# main.net
KiCad netlist of a schematic drawn in EAGLE
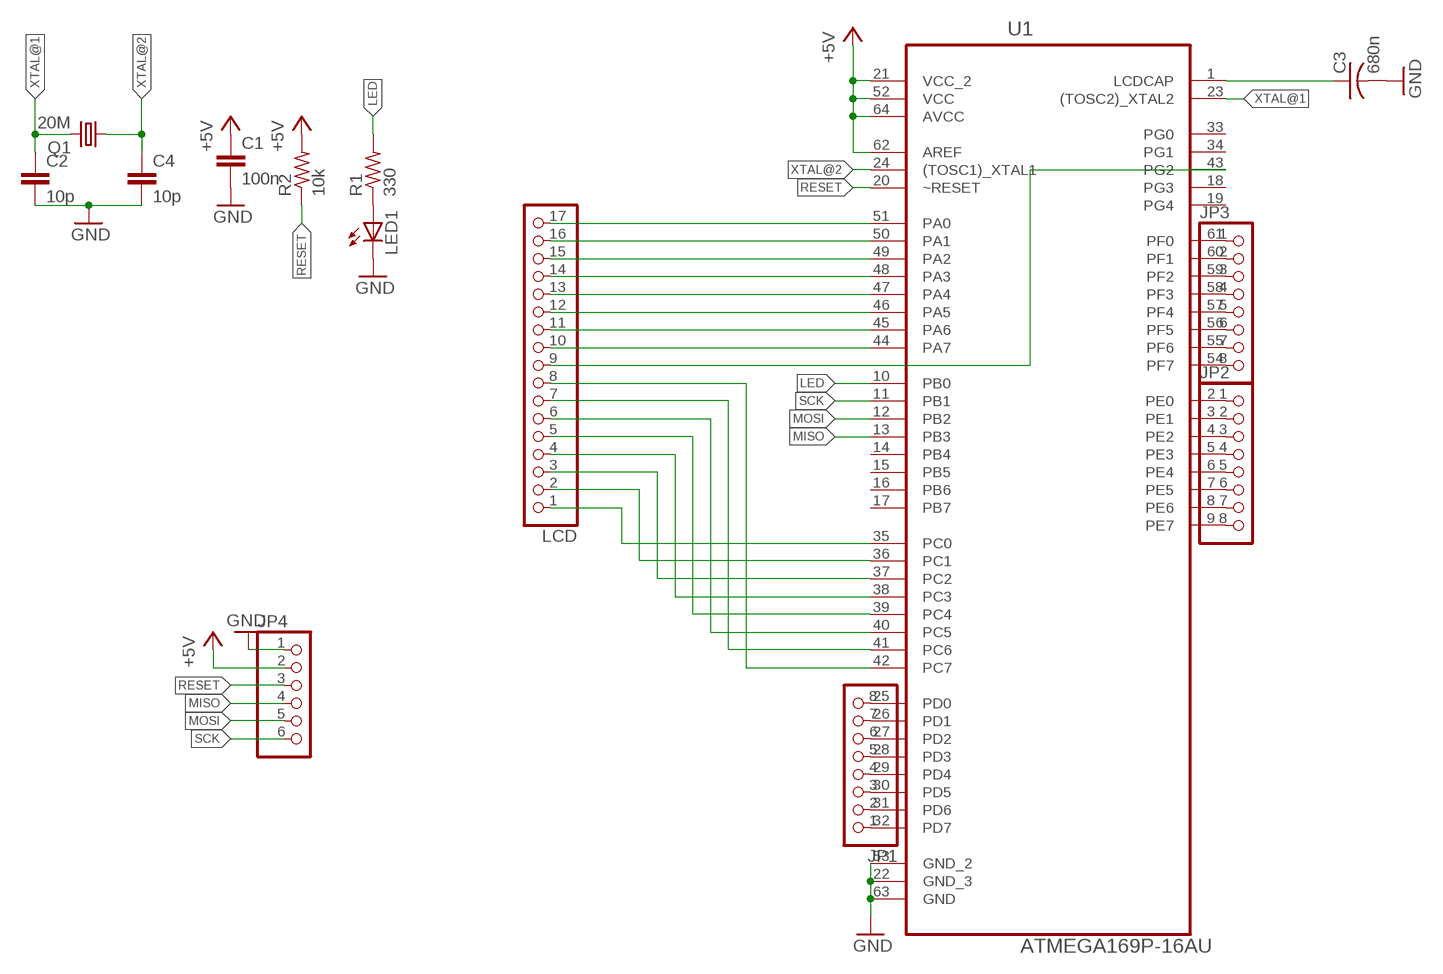
[diagram p0: schematic, sheet 1]

(export (version "E")
  (design (tool "Eeschema 10.0.6"))
  (components
    (comp (ref "C1")
      (value "100n")
      (footprint "eagle-import:C0603")
      (libsource (lib "eagle-import") (part "C-EUC0603"))
    )
    (comp (ref "C2")
      (value "10p")
      (footprint "eagle-import:C0603")
      (libsource (lib "eagle-import") (part "C-EUC0603"))
    )
    (comp (ref "C3")
      (value "680n")
      (footprint "eagle-import:C025-025X050")
      (libsource (lib "eagle-import") (part "C-US025-025X050"))
    )
    (comp (ref "C4")
      (value "10p")
      (footprint "eagle-import:C0603")
      (libsource (lib "eagle-import") (part "C-EUC0603"))
    )
    (comp (ref "JP1")
      (value "PINHD-1X8/90")
      (footprint "eagle-import:1X08_90")
      (libsource (lib "eagle-import") (part "PINHD-1X8/90"))
    )
    (comp (ref "JP2")
      (value "PINHD-1X8/90")
      (footprint "eagle-import:1X08_90")
      (libsource (lib "eagle-import") (part "PINHD-1X8/90"))
    )
    (comp (ref "JP3")
      (value "PINHD-1X8/90")
      (footprint "eagle-import:1X08_90")
      (libsource (lib "eagle-import") (part "PINHD-1X8/90"))
    )
    (comp (ref "JP4")
      (value "PINHD-1X6")
      (footprint "eagle-import:1X06")
      (libsource (lib "eagle-import") (part "PINHD-1X6"))
    )
    (comp (ref "LCD")
      (value "PINHD-1X17")
      (footprint "eagle-import:1X17")
      (libsource (lib "eagle-import") (part "PINHD-1X17"))
    )
    (comp (ref "LED1")
      (value "LEDCHIPLED_0805")
      (footprint "eagle-import:CHIPLED_0805")
      (libsource (lib "eagle-import") (part "LEDCHIPLED_0805"))
    )
    (comp (ref "Q1")
      (value "20M")
      (footprint "eagle-import:HC49UP")
      (libsource (lib "eagle-import") (part "CRYSTALHC49UP"))
    )
    (comp (ref "R1")
      (value "330")
      (footprint "eagle-import:R0603")
      (libsource (lib "eagle-import") (part "R-US_R0603"))
    )
    (comp (ref "R2")
      (value "10k")
      (footprint "eagle-import:R0603")
      (libsource (lib "eagle-import") (part "R-US_R0603"))
    )
    (comp (ref "U1")
      (value "ATMEGA169P-16AU")
      (footprint "eagle-import:QFP80P1600X1600X120-64N")
      (libsource (lib "eagle-import") (part "ATMEGA169P-16AU"))
    )
  )
  (nets
    (net (code "1") (name "+5V") (class "Default")
      (node (ref "C1") (pin "1") (pinfunction "1_1") (pintype "passive"))
      (node (ref "JP4") (pin "2") (pinfunction "2_2") (pintype "passive"))
      (node (ref "R2") (pin "2") (pinfunction "2_2") (pintype "passive"))
      (node (ref "U1") (pin "21") (pinfunction "VCC_2_21") (pintype "power_in"))
      (node (ref "U1") (pin "52") (pinfunction "VCC_52") (pintype "power_in"))
      (node (ref "U1") (pin "62") (pinfunction "AREF_62") (pintype "input"))
      (node (ref "U1") (pin "64") (pinfunction "AVCC_64") (pintype "power_in"))
    )
    (net (code "2") (name "GND") (class "Default")
      (node (ref "C1") (pin "2") (pinfunction "2_2") (pintype "passive"))
      (node (ref "C2") (pin "2") (pinfunction "2_2") (pintype "passive"))
      (node (ref "C3") (pin "2") (pinfunction "2_2") (pintype "passive"))
      (node (ref "C4") (pin "2") (pinfunction "2_2") (pintype "passive"))
      (node (ref "JP4") (pin "1") (pinfunction "1_1") (pintype "passive"))
      (node (ref "LED1") (pin "C") (pinfunction "C_C") (pintype "passive"))
      (node (ref "U1") (pin "22") (pinfunction "GND_3_22") (pintype "passive"))
      (node (ref "U1") (pin "53") (pinfunction "GND_2_53") (pintype "passive"))
      (node (ref "U1") (pin "63") (pinfunction "GND_63") (pintype "passive"))
    )
    (net (code "3") (name "LED") (class "Default")
      (node (ref "R1") (pin "2") (pinfunction "2_2") (pintype "passive"))
      (node (ref "U1") (pin "10") (pinfunction "PB0_10") (pintype "bidirectional"))
    )
    (net (code "4") (name "MISO") (class "Default")
      (node (ref "JP4") (pin "4") (pinfunction "4_4") (pintype "passive"))
      (node (ref "U1") (pin "13") (pinfunction "PB3_13") (pintype "bidirectional"))
    )
    (net (code "5") (name "MOSI") (class "Default")
      (node (ref "JP4") (pin "5") (pinfunction "5_5") (pintype "passive"))
      (node (ref "U1") (pin "12") (pinfunction "PB2_12") (pintype "bidirectional"))
    )
    (net (code "6") (name "Net-(LED1-PadA)") (class "Default")
      (node (ref "LED1") (pin "A") (pinfunction "A_A") (pintype "passive"))
      (node (ref "R1") (pin "1") (pinfunction "1_1") (pintype "passive"))
    )
    (net (code "7") (name "Net-(U1-LCDCAP)") (class "Default")
      (node (ref "C3") (pin "1") (pinfunction "1_1") (pintype "passive"))
      (node (ref "U1") (pin "1") (pinfunction "LCDCAP_1") (pintype "passive"))
    )
    (net (code "8") (name "Net-(U1-PA0)") (class "Default")
      (node (ref "LCD") (pin "17") (pinfunction "17_17") (pintype "passive"))
      (node (ref "U1") (pin "51") (pinfunction "PA0_51") (pintype "bidirectional"))
    )
    (net (code "9") (name "Net-(U1-PA1)") (class "Default")
      (node (ref "LCD") (pin "16") (pinfunction "16_16") (pintype "passive"))
      (node (ref "U1") (pin "50") (pinfunction "PA1_50") (pintype "bidirectional"))
    )
    (net (code "10") (name "Net-(U1-PA2)") (class "Default")
      (node (ref "LCD") (pin "15") (pinfunction "15_15") (pintype "passive"))
      (node (ref "U1") (pin "49") (pinfunction "PA2_49") (pintype "bidirectional"))
    )
    (net (code "11") (name "Net-(U1-PA3)") (class "Default")
      (node (ref "LCD") (pin "14") (pinfunction "14_14") (pintype "passive"))
      (node (ref "U1") (pin "48") (pinfunction "PA3_48") (pintype "bidirectional"))
    )
    (net (code "12") (name "Net-(U1-PA4)") (class "Default")
      (node (ref "LCD") (pin "13") (pinfunction "13_13") (pintype "passive"))
      (node (ref "U1") (pin "47") (pinfunction "PA4_47") (pintype "bidirectional"))
    )
    (net (code "13") (name "Net-(U1-PA5)") (class "Default")
      (node (ref "LCD") (pin "12") (pinfunction "12_12") (pintype "passive"))
      (node (ref "U1") (pin "46") (pinfunction "PA5_46") (pintype "bidirectional"))
    )
    (net (code "14") (name "Net-(U1-PA6)") (class "Default")
      (node (ref "LCD") (pin "11") (pinfunction "11_11") (pintype "passive"))
      (node (ref "U1") (pin "45") (pinfunction "PA6_45") (pintype "bidirectional"))
    )
    (net (code "15") (name "Net-(U1-PA7)") (class "Default")
      (node (ref "LCD") (pin "10") (pinfunction "10_10") (pintype "passive"))
      (node (ref "U1") (pin "44") (pinfunction "PA7_44") (pintype "bidirectional"))
    )
    (net (code "16") (name "Net-(U1-PC0)") (class "Default")
      (node (ref "LCD") (pin "1") (pinfunction "1_1") (pintype "passive"))
      (node (ref "U1") (pin "35") (pinfunction "PC0_35") (pintype "bidirectional"))
    )
    (net (code "17") (name "Net-(U1-PC1)") (class "Default")
      (node (ref "LCD") (pin "2") (pinfunction "2_2") (pintype "passive"))
      (node (ref "U1") (pin "36") (pinfunction "PC1_36") (pintype "bidirectional"))
    )
    (net (code "18") (name "Net-(U1-PC2)") (class "Default")
      (node (ref "LCD") (pin "3") (pinfunction "3_3") (pintype "passive"))
      (node (ref "U1") (pin "37") (pinfunction "PC2_37") (pintype "bidirectional"))
    )
    (net (code "19") (name "Net-(U1-PC3)") (class "Default")
      (node (ref "LCD") (pin "4") (pinfunction "4_4") (pintype "passive"))
      (node (ref "U1") (pin "38") (pinfunction "PC3_38") (pintype "bidirectional"))
    )
    (net (code "20") (name "Net-(U1-PC4)") (class "Default")
      (node (ref "LCD") (pin "5") (pinfunction "5_5") (pintype "passive"))
      (node (ref "U1") (pin "39") (pinfunction "PC4_39") (pintype "bidirectional"))
    )
    (net (code "21") (name "Net-(U1-PC5)") (class "Default")
      (node (ref "LCD") (pin "6") (pinfunction "6_6") (pintype "passive"))
      (node (ref "U1") (pin "40") (pinfunction "PC5_40") (pintype "bidirectional"))
    )
    (net (code "22") (name "Net-(U1-PC6)") (class "Default")
      (node (ref "LCD") (pin "7") (pinfunction "7_7") (pintype "passive"))
      (node (ref "U1") (pin "41") (pinfunction "PC6_41") (pintype "bidirectional"))
    )
    (net (code "23") (name "Net-(U1-PC7)") (class "Default")
      (node (ref "LCD") (pin "8") (pinfunction "8_8") (pintype "passive"))
      (node (ref "U1") (pin "42") (pinfunction "PC7_42") (pintype "bidirectional"))
    )
    (net (code "24") (name "Net-(U1-PD0)") (class "Default")
      (node (ref "JP1") (pin "8") (pinfunction "8_8") (pintype "passive"))
      (node (ref "U1") (pin "25") (pinfunction "PD0_25") (pintype "bidirectional"))
    )
    (net (code "25") (name "Net-(U1-PD1)") (class "Default")
      (node (ref "JP1") (pin "7") (pinfunction "7_7") (pintype "passive"))
      (node (ref "U1") (pin "26") (pinfunction "PD1_26") (pintype "bidirectional"))
    )
    (net (code "26") (name "Net-(U1-PD2)") (class "Default")
      (node (ref "JP1") (pin "6") (pinfunction "6_6") (pintype "passive"))
      (node (ref "U1") (pin "27") (pinfunction "PD2_27") (pintype "bidirectional"))
    )
    (net (code "27") (name "Net-(U1-PD3)") (class "Default")
      (node (ref "JP1") (pin "5") (pinfunction "5_5") (pintype "passive"))
      (node (ref "U1") (pin "28") (pinfunction "PD3_28") (pintype "bidirectional"))
    )
    (net (code "28") (name "Net-(U1-PD4)") (class "Default")
      (node (ref "JP1") (pin "4") (pinfunction "4_4") (pintype "passive"))
      (node (ref "U1") (pin "29") (pinfunction "PD4_29") (pintype "bidirectional"))
    )
    (net (code "29") (name "Net-(U1-PD5)") (class "Default")
      (node (ref "JP1") (pin "3") (pinfunction "3_3") (pintype "passive"))
      (node (ref "U1") (pin "30") (pinfunction "PD5_30") (pintype "bidirectional"))
    )
    (net (code "30") (name "Net-(U1-PD6)") (class "Default")
      (node (ref "JP1") (pin "2") (pinfunction "2_2") (pintype "passive"))
      (node (ref "U1") (pin "31") (pinfunction "PD6_31") (pintype "bidirectional"))
    )
    (net (code "31") (name "Net-(U1-PD7)") (class "Default")
      (node (ref "JP1") (pin "1") (pinfunction "1_1") (pintype "passive"))
      (node (ref "U1") (pin "32") (pinfunction "PD7_32") (pintype "bidirectional"))
    )
    (net (code "32") (name "Net-(U1-PE0)") (class "Default")
      (node (ref "JP2") (pin "1") (pinfunction "1_1") (pintype "passive"))
      (node (ref "U1") (pin "2") (pinfunction "PE0_2") (pintype "bidirectional"))
    )
    (net (code "33") (name "Net-(U1-PE1)") (class "Default")
      (node (ref "JP2") (pin "2") (pinfunction "2_2") (pintype "passive"))
      (node (ref "U1") (pin "3") (pinfunction "PE1_3") (pintype "bidirectional"))
    )
    (net (code "34") (name "Net-(U1-PE2)") (class "Default")
      (node (ref "JP2") (pin "3") (pinfunction "3_3") (pintype "passive"))
      (node (ref "U1") (pin "4") (pinfunction "PE2_4") (pintype "bidirectional"))
    )
    (net (code "35") (name "Net-(U1-PE3)") (class "Default")
      (node (ref "JP2") (pin "4") (pinfunction "4_4") (pintype "passive"))
      (node (ref "U1") (pin "5") (pinfunction "PE3_5") (pintype "bidirectional"))
    )
    (net (code "36") (name "Net-(U1-PE4)") (class "Default")
      (node (ref "JP2") (pin "5") (pinfunction "5_5") (pintype "passive"))
      (node (ref "U1") (pin "6") (pinfunction "PE4_6") (pintype "bidirectional"))
    )
    (net (code "37") (name "Net-(U1-PE5)") (class "Default")
      (node (ref "JP2") (pin "6") (pinfunction "6_6") (pintype "passive"))
      (node (ref "U1") (pin "7") (pinfunction "PE5_7") (pintype "bidirectional"))
    )
    (net (code "38") (name "Net-(U1-PE6)") (class "Default")
      (node (ref "JP2") (pin "7") (pinfunction "7_7") (pintype "passive"))
      (node (ref "U1") (pin "8") (pinfunction "PE6_8") (pintype "bidirectional"))
    )
    (net (code "39") (name "Net-(U1-PE7)") (class "Default")
      (node (ref "JP2") (pin "8") (pinfunction "8_8") (pintype "passive"))
      (node (ref "U1") (pin "9") (pinfunction "PE7_9") (pintype "bidirectional"))
    )
    (net (code "40") (name "Net-(U1-PF0)") (class "Default")
      (node (ref "JP3") (pin "1") (pinfunction "1_1") (pintype "passive"))
      (node (ref "U1") (pin "61") (pinfunction "PF0_61") (pintype "bidirectional"))
    )
    (net (code "41") (name "Net-(U1-PF1)") (class "Default")
      (node (ref "JP3") (pin "2") (pinfunction "2_2") (pintype "passive"))
      (node (ref "U1") (pin "60") (pinfunction "PF1_60") (pintype "bidirectional"))
    )
    (net (code "42") (name "Net-(U1-PF2)") (class "Default")
      (node (ref "JP3") (pin "3") (pinfunction "3_3") (pintype "passive"))
      (node (ref "U1") (pin "59") (pinfunction "PF2_59") (pintype "bidirectional"))
    )
    (net (code "43") (name "Net-(U1-PF3)") (class "Default")
      (node (ref "JP3") (pin "4") (pinfunction "4_4") (pintype "passive"))
      (node (ref "U1") (pin "58") (pinfunction "PF3_58") (pintype "bidirectional"))
    )
    (net (code "44") (name "Net-(U1-PF4)") (class "Default")
      (node (ref "JP3") (pin "5") (pinfunction "5_5") (pintype "passive"))
      (node (ref "U1") (pin "57") (pinfunction "PF4_57") (pintype "bidirectional"))
    )
    (net (code "45") (name "Net-(U1-PF5)") (class "Default")
      (node (ref "JP3") (pin "6") (pinfunction "6_6") (pintype "passive"))
      (node (ref "U1") (pin "56") (pinfunction "PF5_56") (pintype "bidirectional"))
    )
    (net (code "46") (name "Net-(U1-PF6)") (class "Default")
      (node (ref "JP3") (pin "7") (pinfunction "7_7") (pintype "passive"))
      (node (ref "U1") (pin "55") (pinfunction "PF6_55") (pintype "bidirectional"))
    )
    (net (code "47") (name "Net-(U1-PF7)") (class "Default")
      (node (ref "JP3") (pin "8") (pinfunction "8_8") (pintype "passive"))
      (node (ref "U1") (pin "54") (pinfunction "PF7_54") (pintype "bidirectional"))
    )
    (net (code "48") (name "Net-(U1-PG2)") (class "Default")
      (node (ref "LCD") (pin "9") (pinfunction "9_9") (pintype "passive"))
      (node (ref "U1") (pin "43") (pinfunction "PG2_43") (pintype "bidirectional"))
    )
    (net (code "49") (name "RESET") (class "Default")
      (node (ref "JP4") (pin "3") (pinfunction "3_3") (pintype "passive"))
      (node (ref "R2") (pin "1") (pinfunction "1_1") (pintype "passive"))
      (node (ref "U1") (pin "20") (pinfunction "~{RESET}_20") (pintype "input"))
    )
    (net (code "50") (name "SCK") (class "Default")
      (node (ref "JP4") (pin "6") (pinfunction "6_6") (pintype "passive"))
      (node (ref "U1") (pin "11") (pinfunction "PB1_11") (pintype "bidirectional"))
    )
    (net (code "51") (name "XTAL@1") (class "Default")
      (node (ref "C2") (pin "1") (pinfunction "1_1") (pintype "passive"))
      (node (ref "Q1") (pin "2") (pinfunction "2_2") (pintype "passive"))
      (node (ref "U1") (pin "23") (pinfunction "(TOSC2)_XTAL2_23") (pintype "output"))
    )
    (net (code "52") (name "XTAL@2") (class "Default")
      (node (ref "C4") (pin "1") (pinfunction "1_1") (pintype "passive"))
      (node (ref "Q1") (pin "1") (pinfunction "1_1") (pintype "passive"))
      (node (ref "U1") (pin "24") (pinfunction "(TOSC1)_XTAL1_24") (pintype "input"))
    )
    (net (code "53") (name "unconnected-(U1-PB4-Pad14)") (class "Default")
      (node (ref "U1") (pin "14") (pinfunction "PB4_14") (pintype "bidirectional"))
    )
    (net (code "54") (name "unconnected-(U1-PB5-Pad15)") (class "Default")
      (node (ref "U1") (pin "15") (pinfunction "PB5_15") (pintype "bidirectional"))
    )
    (net (code "55") (name "unconnected-(U1-PB6-Pad16)") (class "Default")
      (node (ref "U1") (pin "16") (pinfunction "PB6_16") (pintype "bidirectional"))
    )
    (net (code "56") (name "unconnected-(U1-PB7-Pad17)") (class "Default")
      (node (ref "U1") (pin "17") (pinfunction "PB7_17") (pintype "bidirectional"))
    )
    (net (code "57") (name "unconnected-(U1-PG0-Pad33)") (class "Default")
      (node (ref "U1") (pin "33") (pinfunction "PG0_33") (pintype "bidirectional"))
    )
    (net (code "58") (name "unconnected-(U1-PG1-Pad34)") (class "Default")
      (node (ref "U1") (pin "34") (pinfunction "PG1_34") (pintype "bidirectional"))
    )
    (net (code "59") (name "unconnected-(U1-PG3-Pad18)") (class "Default")
      (node (ref "U1") (pin "18") (pinfunction "PG3_18") (pintype "bidirectional"))
    )
    (net (code "60") (name "unconnected-(U1-PG4-Pad19)") (class "Default")
      (node (ref "U1") (pin "19") (pinfunction "PG4_19") (pintype "bidirectional"))
    )
  )
)
